# Buck.net
KiCad netlist of a schematic drawn in Altium Designer
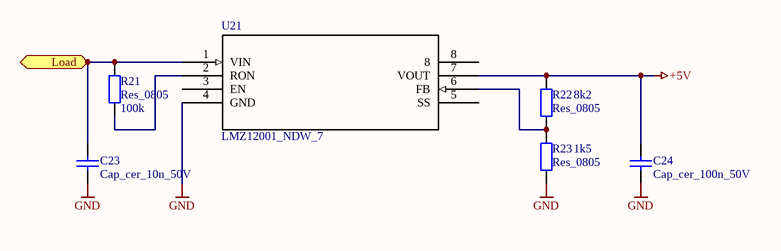
[diagram p0: Buck.SchDoc]

(export (version "E")
  (design (tool "Eeschema 10.0.6"))
  (components
    (comp (ref "C23")
      (value "Cap_cer_10n_50V")
      (footprint "_0805")
      (fields (field (name "VOLTAGE") "50V"))
      (libsource (lib "Capacitors$") (part "Cap_120"))
    )
    (comp (ref "C24")
      (value "Cap_cer_100n_50V")
      (footprint "_0805")
      (fields (field (name "VOLTAGE") "50V"))
      (libsource (lib "Capacitors$") (part "Cap_124"))
    )
    (comp (ref "R21")
      (value "Res_0805")
      (footprint "_0805")
      (fields (field (name "ALTIUM_VALUE") "100k"))
      (libsource (lib "") (part "Res_6_1"))
    )
    (comp (ref "R22")
      (value "Res_0805")
      (footprint "_0805")
      (fields (field (name "ALTIUM_VALUE") "8k2"))
      (libsource (lib "Resistors$") (part "Res_6"))
    )
    (comp (ref "R23")
      (value "Res_0805")
      (footprint "_0805")
      (fields (field (name "ALTIUM_VALUE") "1k5"))
      (libsource (lib "Resistors$") (part "Res_6"))
    )
    (comp (ref "U21")
      (value "LMZ12001_NDW_7")
      (footprint "TZA07A")
      (description "Imported")
      (fields
        (field (name "MANUFACTURER") "Texas Instruments")
        (field (name "MANUFACTURER_PART_NUMBER") "lmz12001_ndw_7")
      )
      (libsource (lib "LMZ12001") (part "LMZ12001_NDW_7"))
    )
  )
  (nets
    (net (code "1") (name "+5V") (class "Default")
      (node (ref "C24") (pin "2") (pinfunction "2_2") (pintype "passive"))
      (node (ref "R22") (pin "1") (pinfunction "1_1") (pintype "passive"))
      (node (ref "U21") (pin "7") (pinfunction "VOUT_7") (pintype "power_in"))
    )
    (net (code "2") (name "/Load") (class "Default")
      (node (ref "C23") (pin "1") (pinfunction "1_1") (pintype "passive"))
      (node (ref "R21") (pin "2") (pinfunction "2_2") (pintype "passive"))
      (node (ref "U21") (pin "1") (pinfunction "VIN_1") (pintype "input"))
    )
    (net (code "3") (name "GND") (class "Default")
      (node (ref "C23") (pin "2") (pinfunction "2_2") (pintype "passive"))
      (node (ref "C24") (pin "1") (pinfunction "1_1") (pintype "passive"))
      (node (ref "R23") (pin "2") (pinfunction "2_2") (pintype "passive"))
      (node (ref "U21") (pin "4") (pinfunction "GND_4") (pintype "power_in"))
    )
    (net (code "4") (name "Net-(U21-FB)") (class "Default")
      (node (ref "R22") (pin "2") (pinfunction "2_2") (pintype "passive"))
      (node (ref "R23") (pin "1") (pinfunction "1_1") (pintype "passive"))
      (node (ref "U21") (pin "6") (pinfunction "FB_6") (pintype "input"))
    )
    (net (code "5") (name "Net-(U21-RON)") (class "Default")
      (node (ref "R21") (pin "1") (pinfunction "1_1") (pintype "passive"))
      (node (ref "U21") (pin "2") (pinfunction "RON_2") (pintype "passive"))
    )
    (net (code "6") (name "unconnected-(U21-EN-Pad3)") (class "Default")
      (node (ref "U21") (pin "3") (pinfunction "EN_3") (pintype "passive"))
    )
    (net (code "7") (name "unconnected-(U21-Pad8)") (class "Default")
      (node (ref "U21") (pin "8") (pinfunction "8_8") (pintype "passive"))
    )
    (net (code "8") (name "unconnected-(U21-SS-Pad5)") (class "Default")
      (node (ref "U21") (pin "5") (pinfunction "SS_5") (pintype "passive"))
    )
  )
)
